# Schematic.net
KiCad netlist of a schematic drawn in Altium Designer
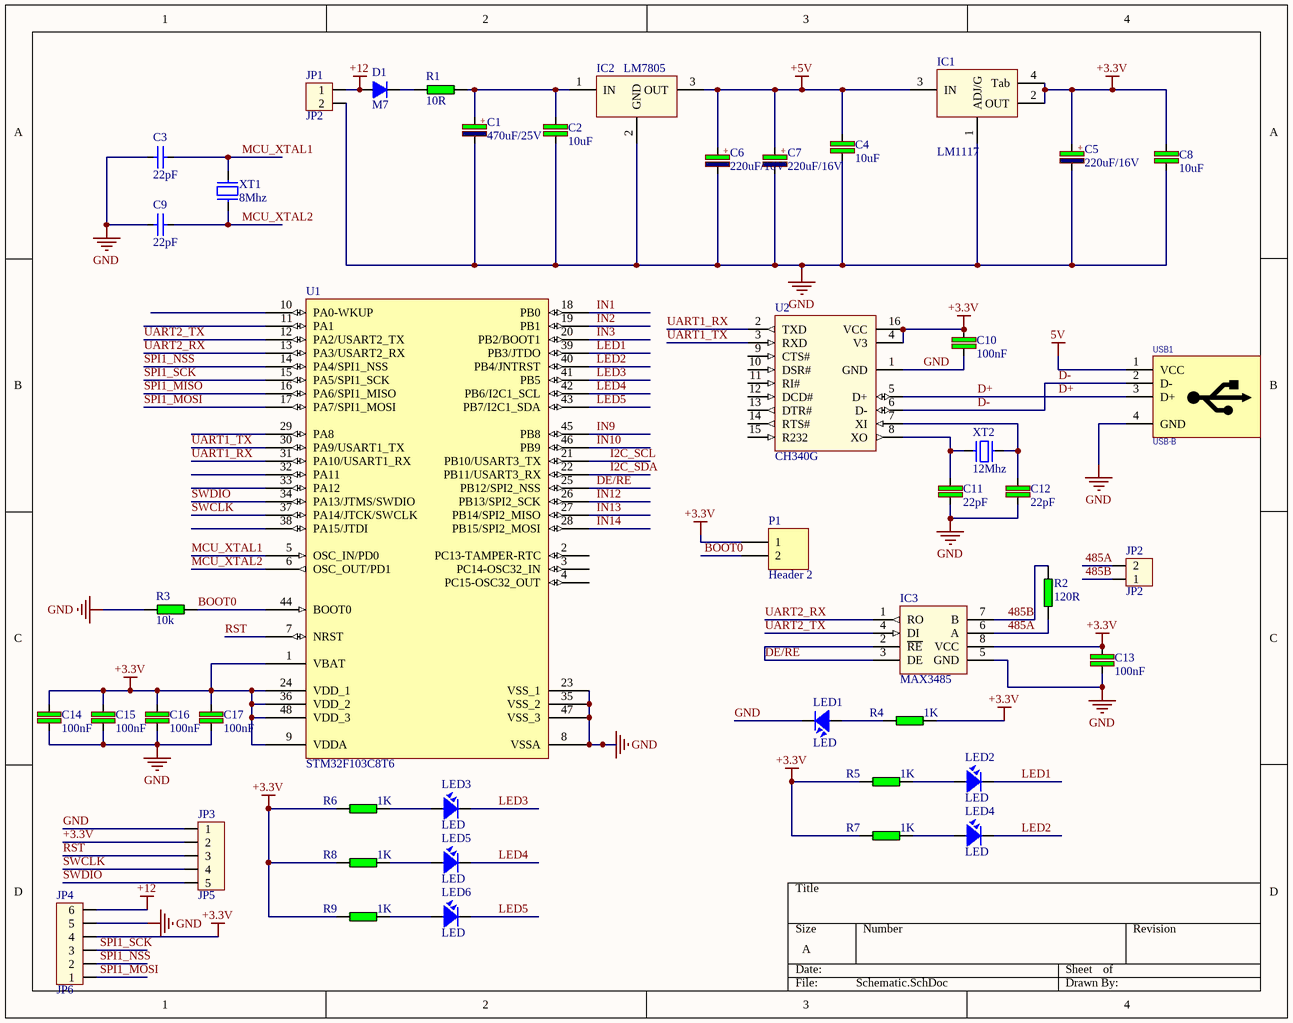
[diagram p0: Schematic.SchDoc]

(export (version "E")
  (design (tool "Eeschema 10.0.6"))
  (components
    (comp (ref "C1")
      (value "470uF/25V")
      (footprint "CP_1000UF/25V_NAM - cao")
      (description "470uF/35V")
      (fields (field (name "MANUFACTURER") "Würth Elektronik") (field (name "PART NUMBER") "860020575014"))
      (libsource (lib "Anh_Trung") (part "CP4"))
    )
    (comp (ref "C2")
      (value "10uF")
      (footprint "C-0805")
      (description "Cap SMD")
      (libsource (lib "") (part "C_1"))
    )
    (comp (ref "C3")
      (value "22pF")
      (footprint "CAP_0805")
      (description "Capacitor")
      (fields (field (name "PUBLISHER") "Altium Limited"))
      (libsource (lib "My Library") (part "CapSMD"))
    )
    (comp (ref "C4")
      (value "10uF")
      (footprint "C-0805")
      (description "Cap SMD")
      (libsource (lib "") (part "C_1"))
    )
    (comp (ref "C5")
      (value "220uF/16V")
      (footprint "CA-ALU-5L")
      (description "Cap 100uF/35V - 470uF/16V")
      (libsource (lib "Anh_Trung") (part "CP3"))
    )
    (comp (ref "C6")
      (value "220uF/16V")
      (footprint "CA-ALU-5L")
      (description "Cap 100uF/35V - 470uF/16V")
      (libsource (lib "Anh_Trung") (part "CP3"))
    )
    (comp (ref "C7")
      (value "220uF/16V")
      (footprint "CA-ALU-5L")
      (description "Cap 100uF/35V - 470uF/16V")
      (libsource (lib "Anh_Trung") (part "CP3"))
    )
    (comp (ref "C8")
      (value "10uF")
      (footprint "C-0805")
      (description "Cap SMD")
      (libsource (lib "") (part "C_1"))
    )
    (comp (ref "C9")
      (value "22pF")
      (footprint "CAP_0805")
      (description "Capacitor")
      (fields (field (name "PUBLISHER") "Altium Limited"))
      (libsource (lib "My Library") (part "CapSMD"))
    )
    (comp (ref "C10")
      (value "100nF")
      (footprint "C-0805")
      (description "Cap SMD")
      (fields
        (field (name "MANUFACTURER") "Samsung Electro-Mechanics")
        (field (name "PART NUMBER") "CL21B104KBCNNWC")
      )
      (libsource (lib "") (part "C_1"))
    )
    (comp (ref "C11")
      (value "22pF")
      (footprint "C-0805")
      (description "Cap SMD")
      (fields
        (field (name "MANUFACTURER") "Samsung Electro-Mechanics")
        (field (name "PART NUMBER") "CL21C220JBANFNC")
      )
      (libsource (lib "") (part "C_1"))
    )
    (comp (ref "C12")
      (value "22pF")
      (footprint "C-0805")
      (description "Cap SMD")
      (fields
        (field (name "MANUFACTURER") "Samsung Electro-Mechanics")
        (field (name "PART NUMBER") "CL21C220JBANFNC")
      )
      (libsource (lib "") (part "C_1"))
    )
    (comp (ref "C13")
      (value "100nF")
      (footprint "C-0805")
      (description "Cap SMD")
      (fields
        (field (name "MANUFACTURER") "Samsung Electro-Mechanics")
        (field (name "PART NUMBER") "CL21B104KBCNNWC")
      )
      (libsource (lib "Anh_Trung") (part "C"))
    )
    (comp (ref "C14")
      (value "100nF")
      (footprint "C-0805")
      (description "Cap SMD")
      (libsource (lib "heromap") (part "C"))
    )
    (comp (ref "C15")
      (value "100nF")
      (footprint "C-0805")
      (description "Cap SMD")
      (libsource (lib "heromap") (part "C"))
    )
    (comp (ref "C16")
      (value "100nF")
      (footprint "C-0805")
      (description "Cap SMD")
      (libsource (lib "heromap") (part "C"))
    )
    (comp (ref "C17")
      (value "100nF")
      (footprint "C-0805")
      (description "Cap SMD")
      (libsource (lib "heromap") (part "C"))
    )
    (comp (ref "D1")
      (value "M7")
      (footprint "SMA11")
      (description "Diode 1A")
      (libsource (lib "Anh_Trung") (part "D1A"))
    )
    (comp (ref "IC1")
      (value "LM1117")
      (footprint "SOT223-4N")
      (description "3v3")
      (libsource (lib "My Library") (part "LM1117"))
    )
    (comp (ref "IC2")
      (value "LM7805")
      (footprint "TO-252 7805")
      (description "On ap +, from + 5 to + 24VDC")
      (libsource (lib "Anh_Trung") (part "LM78xx"))
    )
    (comp (ref "IC3")
      (value "MAX3485")
      (footprint "SOIC-8")
      (description "IC TRANSCEIVER HALF 1/1 SOT23-8")
      (fields (field (name "MANUFACTURER") "Maxim Integrated") (field (name "PART NUMBER") "MAX3362EKA+T"))
      (libsource (lib "Anh_Trung") (part "MAX3362EKA+T"))
    )
    (comp (ref "JP1")
      (value "JP2")
      (footprint "KF2-5.08T")
      (description "Connector 2")
      (libsource (lib "") (part "Con2_1"))
    )
    (comp (ref "JP2")
      (value "JP2")
      (footprint "KF2-5.08T")
      (description "Connector 2")
      (libsource (lib "Anh_Trung") (part "Con2"))
    )
    (comp (ref "JP3")
      (value "JP5")
      (footprint "JP5-D1T")
      (description "Connector 5")
      (libsource (lib "Anh_Trung") (part "Con5"))
    )
    (comp (ref "JP4")
      (value "JP6")
      (footprint "CON6")
      (description "Connector 6")
      (libsource (lib "My Library") (part "Con6"))
    )
    (comp (ref "LED1")
      (value "LED")
      (footprint "LED-0805-Red")
      (description "LED Single colour Green and Red")
      (libsource (lib "My Library") (part "LED"))
    )
    (comp (ref "LED2")
      (value "LED")
      (footprint "LED-0805-Red")
      (description "LED Single colour Green and Red")
      (libsource (lib "My Library") (part "LED"))
    )
    (comp (ref "LED3")
      (value "LED")
      (footprint "LED-3")
      (description "LED Single colour Green and Red")
      (libsource (lib "VioletofSun") (part "LED"))
    )
    (comp (ref "LED4")
      (value "LED")
      (footprint "LED-0805-Red")
      (description "LED Single colour Green and Red")
      (libsource (lib "My Library") (part "LED"))
    )
    (comp (ref "LED5")
      (value "LED")
      (footprint "LED-3")
      (description "LED Single colour Green and Red")
      (libsource (lib "VioletofSun") (part "LED"))
    )
    (comp (ref "LED6")
      (value "LED")
      (footprint "LED-3")
      (description "LED Single colour Green and Red")
      (libsource (lib "VioletofSun") (part "LED"))
    )
    (comp (ref "P1")
      (value "Header 2")
      (footprint "HDR1X2")
      (description "Header, 2-Pin")
      (fields (field (name "PUBLISHER") "Altium Limited"))
      (libsource (lib "My Library") (part "Header 2"))
    )
    (comp (ref "R1")
      (value "10R")
      (footprint "R-1206")
      (description "Resistor 1/4W")
      (libsource (lib "") (part "RES_1"))
    )
    (comp (ref "R2")
      (value "120R")
      (footprint "R-0805")
      (description "Resistor 1/4W")
      (libsource (lib "heromap") (part "RES"))
    )
    (comp (ref "R3")
      (value "10k")
      (footprint "R-0805")
      (description "Resistor 1/4W")
      (libsource (lib "") (part "RES_3"))
    )
    (comp (ref "R4")
      (value "1K")
      (footprint "R-0805")
      (description "Resistor 1/4W")
      (libsource (lib "") (part "RES_2"))
    )
    (comp (ref "R5")
      (value "1K")
      (footprint "R-0805")
      (description "Resistor 1/4W")
      (libsource (lib "") (part "RES_2"))
    )
    (comp (ref "R6")
      (value "1K")
      (footprint "R-0805")
      (description "Resistor 1/4W")
      (libsource (lib "") (part "RES_2"))
    )
    (comp (ref "R7")
      (value "1K")
      (footprint "R-0805")
      (description "Resistor 1/4W")
      (libsource (lib "") (part "RES_2"))
    )
    (comp (ref "R8")
      (value "1K")
      (footprint "R-0805")
      (description "Resistor 1/4W")
      (libsource (lib "") (part "RES_2"))
    )
    (comp (ref "R9")
      (value "1K")
      (footprint "R-0805")
      (description "Resistor 1/4W")
      (libsource (lib "") (part "RES_2"))
    )
    (comp (ref "U1")
      (value "STM32F103C8T6")
      (footprint "LQFP48_L")
      (libsource (lib "heromap") (part "STM32F103C8T6"))
    )
    (comp (ref "U2")
      (value "CH340G")
      (footprint "SOIC-16")
      (description "USB to UART Interface")
      (fields (field (name "MANUFACTURER") "WCH"))
      (libsource (lib "Anh_Trung") (part "CH340G"))
    )
    (comp (ref "USB1")
      (value "USB-B")
      (footprint "USB-B")
      (description "CONN USB 2.0 RT ANGLE TYPE B")
      (fields (field (name "MANUFACTURER") "Stewart Connector") (field (name "PART NUMBER") "SS-52300-001"))
      (libsource (lib "Anh_Trung") (part "USB-B"))
    )
    (comp (ref "XT1")
      (value "8Mhz")
      (footprint "XTAL-RU49/4")
      (description "CRYSTAL 12.0000MHZ 18PF SMD")
      (fields
        (field (name "MANUFACTURER") "IQD Frequency Products")
        (field (name "PART NUMBER") "LFXTAL036356REEL")
      )
      (libsource (lib "Anh_Trung") (part "XT2"))
    )
    (comp (ref "XT2")
      (value "12Mhz")
      (footprint "XTAL-RU49/4")
      (description "CRYSTAL 12.0000MHZ 18PF SMD")
      (fields
        (field (name "MANUFACTURER") "IQD Frequency Products")
        (field (name "PART NUMBER") "LFXTAL036356REEL")
      )
      (libsource (lib "Anh_Trung") (part "XT2"))
    )
  )
  (nets
    (net (code "1") (name "+3.3V") (class "Default")
      (node (ref "C10") (pin "2") (pinfunction "2_2") (pintype "passive"))
      (node (ref "C13") (pin "1") (pinfunction "1_1") (pintype "passive"))
      (node (ref "C14") (pin "1") (pinfunction "1_1") (pintype "passive"))
      (node (ref "C15") (pin "1") (pinfunction "1_1") (pintype "passive"))
      (node (ref "C16") (pin "1") (pinfunction "1_1") (pintype "passive"))
      (node (ref "C17") (pin "1") (pinfunction "1_1") (pintype "passive"))
      (node (ref "C5") (pin "1") (pinfunction "1_1") (pintype "passive"))
      (node (ref "C8") (pin "2") (pinfunction "2_2") (pintype "passive"))
      (node (ref "IC1") (pin "2") (pinfunction "OUT_2") (pintype "passive"))
      (node (ref "IC1") (pin "4") (pinfunction "Tab_4") (pintype "passive"))
      (node (ref "IC3") (pin "8") (pinfunction "VCC_8") (pintype "passive"))
      (node (ref "JP3") (pin "2") (pinfunction "2_2") (pintype "passive"))
      (node (ref "JP4") (pin "4") (pinfunction "4_4") (pintype "passive"))
      (node (ref "P1") (pin "1") (pinfunction "1_1") (pintype "passive"))
      (node (ref "R4") (pin "1") (pinfunction "1_1") (pintype "passive"))
      (node (ref "R5") (pin "2") (pinfunction "2_2") (pintype "passive"))
      (node (ref "R6") (pin "2") (pinfunction "2_2") (pintype "passive"))
      (node (ref "R7") (pin "2") (pinfunction "2_2") (pintype "passive"))
      (node (ref "R8") (pin "2") (pinfunction "2_2") (pintype "passive"))
      (node (ref "R9") (pin "2") (pinfunction "2_2") (pintype "passive"))
      (node (ref "U1") (pin "1") (pinfunction "VBAT_1") (pintype "power_in"))
      (node (ref "U1") (pin "24") (pinfunction "VDD_1_24") (pintype "power_in"))
      (node (ref "U1") (pin "36") (pinfunction "VDD_2_36") (pintype "power_in"))
      (node (ref "U1") (pin "48") (pinfunction "VDD_3_48") (pintype "power_in"))
      (node (ref "U1") (pin "9") (pinfunction "VDDA_9") (pintype "power_in"))
      (node (ref "U2") (pin "16") (pinfunction "VCC_16") (pintype "power_in"))
      (node (ref "U2") (pin "4") (pinfunction "V3_4") (pintype "passive"))
    )
    (net (code "2") (name "+5V") (class "Default")
      (node (ref "C4") (pin "2") (pinfunction "2_2") (pintype "passive"))
      (node (ref "C6") (pin "1") (pinfunction "1_1") (pintype "passive"))
      (node (ref "C7") (pin "1") (pinfunction "1_1") (pintype "passive"))
      (node (ref "IC1") (pin "3") (pinfunction "IN_3") (pintype "passive"))
      (node (ref "IC2") (pin "3") (pinfunction "OUT_3") (pintype "passive"))
    )
    (net (code "3") (name "+12") (class "Default")
      (node (ref "D1") (pin "1") (pinfunction "A_1") (pintype "passive"))
      (node (ref "JP1") (pin "1") (pinfunction "1_1") (pintype "passive"))
      (node (ref "JP4") (pin "6") (pinfunction "6_6") (pintype "passive"))
    )
    (net (code "4") (name "/485A") (class "Default")
      (node (ref "IC3") (pin "6") (pinfunction "A_6") (pintype "passive"))
      (node (ref "JP2") (pin "2") (pinfunction "2_2") (pintype "passive"))
      (node (ref "R2") (pin "2") (pinfunction "2_2") (pintype "passive"))
    )
    (net (code "5") (name "/485B") (class "Default")
      (node (ref "IC3") (pin "7") (pinfunction "B_7") (pintype "passive"))
      (node (ref "JP2") (pin "1") (pinfunction "1_1") (pintype "passive"))
      (node (ref "R2") (pin "1") (pinfunction "1_1") (pintype "passive"))
    )
    (net (code "6") (name "/BOOT0") (class "Default")
      (node (ref "P1") (pin "2") (pinfunction "2_2") (pintype "passive"))
      (node (ref "R3") (pin "2") (pinfunction "2_2") (pintype "passive"))
      (node (ref "U1") (pin "44") (pinfunction "BOOT0_44") (pintype "input"))
    )
    (net (code "7") (name "/D+") (class "Default")
      (node (ref "U2") (pin "5") (pinfunction "D+_5") (pintype "bidirectional"))
      (node (ref "USB1") (pin "3") (pinfunction "D+_3") (pintype "passive"))
    )
    (net (code "8") (name "/D-") (class "Default")
      (node (ref "U2") (pin "6") (pinfunction "D-_6") (pintype "bidirectional"))
      (node (ref "USB1") (pin "2") (pinfunction "D-_2") (pintype "passive"))
    )
    (net (code "9") (name "/DE{slash}RE") (class "Default")
      (node (ref "IC3") (pin "2") (pinfunction "~{RE}_2") (pintype "passive"))
      (node (ref "IC3") (pin "3") (pinfunction "DE_3") (pintype "passive"))
      (node (ref "U1") (pin "25") (pinfunction "PB12/SPI2_NSS_25") (pintype "bidirectional"))
    )
    (net (code "10") (name "/I2C_SCL") (class "Default")
      (node (ref "U1") (pin "21") (pinfunction "PB10/USART3_TX_21") (pintype "bidirectional"))
    )
    (net (code "11") (name "/I2C_SDA") (class "Default")
      (node (ref "U1") (pin "22") (pinfunction "PB11/USART3_RX_22") (pintype "bidirectional"))
    )
    (net (code "12") (name "/IN1") (class "Default")
      (node (ref "U1") (pin "18") (pinfunction "PB0_18") (pintype "bidirectional"))
    )
    (net (code "13") (name "/IN2") (class "Default")
      (node (ref "U1") (pin "19") (pinfunction "PB1_19") (pintype "bidirectional"))
    )
    (net (code "14") (name "/IN3") (class "Default")
      (node (ref "U1") (pin "20") (pinfunction "PB2/BOOT1_20") (pintype "bidirectional"))
    )
    (net (code "15") (name "/IN9") (class "Default")
      (node (ref "U1") (pin "45") (pinfunction "PB8_45") (pintype "bidirectional"))
    )
    (net (code "16") (name "/IN10") (class "Default")
      (node (ref "U1") (pin "46") (pinfunction "PB9_46") (pintype "bidirectional"))
    )
    (net (code "17") (name "/IN12") (class "Default")
      (node (ref "U1") (pin "26") (pinfunction "PB13/SPI2_SCK_26") (pintype "bidirectional"))
    )
    (net (code "18") (name "/IN13") (class "Default")
      (node (ref "U1") (pin "27") (pinfunction "PB14/SPI2_MISO_27") (pintype "bidirectional"))
    )
    (net (code "19") (name "/IN14") (class "Default")
      (node (ref "U1") (pin "28") (pinfunction "PB15/SPI2_MOSI_28") (pintype "bidirectional"))
    )
    (net (code "20") (name "/LED1") (class "Default")
      (node (ref "LED2") (pin "2") (pinfunction "2_2") (pintype "passive"))
      (node (ref "U1") (pin "39") (pinfunction "PB3/JTDO_39") (pintype "bidirectional"))
    )
    (net (code "21") (name "/LED2") (class "Default")
      (node (ref "LED4") (pin "2") (pinfunction "2_2") (pintype "passive"))
      (node (ref "U1") (pin "40") (pinfunction "PB4/JNTRST_40") (pintype "bidirectional"))
    )
    (net (code "22") (name "/LED3") (class "Default")
      (node (ref "LED3") (pin "2") (pinfunction "2_2") (pintype "passive"))
      (node (ref "U1") (pin "41") (pinfunction "PB5_41") (pintype "bidirectional"))
    )
    (net (code "23") (name "/LED4") (class "Default")
      (node (ref "LED5") (pin "2") (pinfunction "2_2") (pintype "passive"))
      (node (ref "U1") (pin "42") (pinfunction "PB6/I2C1_SCL_42") (pintype "bidirectional"))
    )
    (net (code "24") (name "/LED5") (class "Default")
      (node (ref "LED6") (pin "2") (pinfunction "2_2") (pintype "passive"))
      (node (ref "U1") (pin "43") (pinfunction "PB7/I2C1_SDA_43") (pintype "bidirectional"))
    )
    (net (code "25") (name "/MCU_XTAL1") (class "Default")
      (node (ref "C3") (pin "1") (pinfunction "1_1") (pintype "passive"))
      (node (ref "U1") (pin "5") (pinfunction "OSC_IN/PD0_5") (pintype "input"))
      (node (ref "XT1") (pin "1") (pinfunction "1_1") (pintype "passive"))
    )
    (net (code "26") (name "/MCU_XTAL2") (class "Default")
      (node (ref "C9") (pin "1") (pinfunction "1_1") (pintype "passive"))
      (node (ref "U1") (pin "6") (pinfunction "OSC_OUT/PD1_6") (pintype "output"))
      (node (ref "XT1") (pin "2") (pinfunction "2_2") (pintype "passive"))
    )
    (net (code "27") (name "/RST") (class "Default")
      (node (ref "JP3") (pin "3") (pinfunction "3_3") (pintype "passive"))
      (node (ref "U1") (pin "7") (pinfunction "NRST_7") (pintype "bidirectional"))
    )
    (net (code "28") (name "/SPI1_MISO") (class "Default")
      (node (ref "U1") (pin "16") (pinfunction "PA6/SPI1_MISO_16") (pintype "bidirectional"))
    )
    (net (code "29") (name "/SPI1_MOSI") (class "Default")
      (node (ref "JP4") (pin "1") (pinfunction "1_1") (pintype "passive"))
      (node (ref "U1") (pin "17") (pinfunction "PA7/SPI1_MOSI_17") (pintype "bidirectional"))
    )
    (net (code "30") (name "/SPI1_NSS") (class "Default")
      (node (ref "JP4") (pin "2") (pinfunction "2_2") (pintype "passive"))
      (node (ref "U1") (pin "14") (pinfunction "PA4/SPI1_NSS_14") (pintype "bidirectional"))
    )
    (net (code "31") (name "/SPI1_SCK") (class "Default")
      (node (ref "JP4") (pin "3") (pinfunction "3_3") (pintype "passive"))
      (node (ref "U1") (pin "15") (pinfunction "PA5/SPI1_SCK_15") (pintype "bidirectional"))
    )
    (net (code "32") (name "/SWCLK") (class "Default")
      (node (ref "JP3") (pin "4") (pinfunction "4_4") (pintype "passive"))
      (node (ref "U1") (pin "37") (pinfunction "PA14/JTCK/SWCLK_37") (pintype "bidirectional"))
    )
    (net (code "33") (name "/SWDIO") (class "Default")
      (node (ref "JP3") (pin "5") (pinfunction "5_5") (pintype "passive"))
      (node (ref "U1") (pin "34") (pinfunction "PA13/JTMS/SWDIO_34") (pintype "bidirectional"))
    )
    (net (code "34") (name "/UART1_RX") (class "Default")
      (node (ref "U1") (pin "31") (pinfunction "PA10/USART1_RX_31") (pintype "bidirectional"))
      (node (ref "U2") (pin "2") (pinfunction "TXD_2") (pintype "output"))
    )
    (net (code "35") (name "/UART1_TX") (class "Default")
      (node (ref "U1") (pin "30") (pinfunction "PA9/USART1_TX_30") (pintype "bidirectional"))
      (node (ref "U2") (pin "3") (pinfunction "RXD_3") (pintype "input"))
    )
    (net (code "36") (name "/UART2_RX") (class "Default")
      (node (ref "IC3") (pin "1") (pinfunction "RO_1") (pintype "output"))
      (node (ref "U1") (pin "13") (pinfunction "PA3/USART2_RX_13") (pintype "bidirectional"))
    )
    (net (code "37") (name "/UART2_TX") (class "Default")
      (node (ref "IC3") (pin "4") (pinfunction "DI_4") (pintype "input"))
      (node (ref "U1") (pin "12") (pinfunction "PA2/USART2_TX_12") (pintype "bidirectional"))
    )
    (net (code "38") (name "5V") (class "Default")
      (node (ref "USB1") (pin "1") (pinfunction "VCC_1") (pintype "passive"))
    )
    (net (code "39") (name "GND") (class "Default")
      (node (ref "C1") (pin "2") (pinfunction "2_2") (pintype "passive"))
      (node (ref "C10") (pin "1") (pinfunction "1_1") (pintype "passive"))
      (node (ref "C11") (pin "1") (pinfunction "1_1") (pintype "passive"))
      (node (ref "C12") (pin "1") (pinfunction "1_1") (pintype "passive"))
      (node (ref "C13") (pin "2") (pinfunction "2_2") (pintype "passive"))
      (node (ref "C14") (pin "2") (pinfunction "2_2") (pintype "passive"))
      (node (ref "C15") (pin "2") (pinfunction "2_2") (pintype "passive"))
      (node (ref "C16") (pin "2") (pinfunction "2_2") (pintype "passive"))
      (node (ref "C17") (pin "2") (pinfunction "2_2") (pintype "passive"))
      (node (ref "C2") (pin "1") (pinfunction "1_1") (pintype "passive"))
      (node (ref "C3") (pin "2") (pinfunction "2_2") (pintype "passive"))
      (node (ref "C4") (pin "1") (pinfunction "1_1") (pintype "passive"))
      (node (ref "C5") (pin "2") (pinfunction "2_2") (pintype "passive"))
      (node (ref "C6") (pin "2") (pinfunction "2_2") (pintype "passive"))
      (node (ref "C7") (pin "2") (pinfunction "2_2") (pintype "passive"))
      (node (ref "C8") (pin "1") (pinfunction "1_1") (pintype "passive"))
      (node (ref "C9") (pin "2") (pinfunction "2_2") (pintype "passive"))
      (node (ref "IC1") (pin "1") (pinfunction "ADJ/G_1") (pintype "passive"))
      (node (ref "IC2") (pin "2") (pinfunction "GND_2") (pintype "passive"))
      (node (ref "IC3") (pin "5") (pinfunction "GND_5") (pintype "passive"))
      (node (ref "JP1") (pin "2") (pinfunction "2_2") (pintype "passive"))
      (node (ref "JP3") (pin "1") (pinfunction "1_1") (pintype "passive"))
      (node (ref "JP4") (pin "5") (pinfunction "5_5") (pintype "passive"))
      (node (ref "LED1") (pin "2") (pinfunction "2_2") (pintype "passive"))
      (node (ref "R3") (pin "1") (pinfunction "1_1") (pintype "passive"))
      (node (ref "U1") (pin "23") (pinfunction "VSS_1_23") (pintype "power_in"))
      (node (ref "U1") (pin "35") (pinfunction "VSS_2_35") (pintype "power_in"))
      (node (ref "U1") (pin "47") (pinfunction "VSS_3_47") (pintype "power_in"))
      (node (ref "U1") (pin "8") (pinfunction "VSSA_8") (pintype "power_in"))
      (node (ref "U2") (pin "1") (pinfunction "GND_1") (pintype "passive"))
      (node (ref "USB1") (pin "4") (pinfunction "GND_4") (pintype "passive"))
    )
    (net (code "40") (name "Net-(D1-K)") (class "Default")
      (node (ref "D1") (pin "2") (pinfunction "K_2") (pintype "passive"))
      (node (ref "R1") (pin "1") (pinfunction "1_1") (pintype "passive"))
    )
    (net (code "41") (name "Net-(IC2-IN)") (class "Default")
      (node (ref "C1") (pin "1") (pinfunction "1_1") (pintype "passive"))
      (node (ref "C2") (pin "2") (pinfunction "2_2") (pintype "passive"))
      (node (ref "IC2") (pin "1") (pinfunction "IN_1") (pintype "passive"))
      (node (ref "R1") (pin "2") (pinfunction "2_2") (pintype "passive"))
    )
    (net (code "42") (name "Net-(LED1-Pad1)") (class "Default")
      (node (ref "LED1") (pin "1") (pinfunction "1_1") (pintype "passive"))
      (node (ref "R4") (pin "2") (pinfunction "2_2") (pintype "passive"))
    )
    (net (code "43") (name "Net-(LED2-Pad1)") (class "Default")
      (node (ref "LED2") (pin "1") (pinfunction "1_1") (pintype "passive"))
      (node (ref "R5") (pin "1") (pinfunction "1_1") (pintype "passive"))
    )
    (net (code "44") (name "Net-(LED3-Pad1)") (class "Default")
      (node (ref "LED3") (pin "1") (pinfunction "1_1") (pintype "passive"))
      (node (ref "R6") (pin "1") (pinfunction "1_1") (pintype "passive"))
    )
    (net (code "45") (name "Net-(LED4-Pad1)") (class "Default")
      (node (ref "LED4") (pin "1") (pinfunction "1_1") (pintype "passive"))
      (node (ref "R7") (pin "1") (pinfunction "1_1") (pintype "passive"))
    )
    (net (code "46") (name "Net-(LED5-Pad1)") (class "Default")
      (node (ref "LED5") (pin "1") (pinfunction "1_1") (pintype "passive"))
      (node (ref "R8") (pin "1") (pinfunction "1_1") (pintype "passive"))
    )
    (net (code "47") (name "Net-(LED6-Pad1)") (class "Default")
      (node (ref "LED6") (pin "1") (pinfunction "1_1") (pintype "passive"))
      (node (ref "R9") (pin "1") (pinfunction "1_1") (pintype "passive"))
    )
    (net (code "48") (name "Net-(U2-XI)") (class "Default")
      (node (ref "C12") (pin "2") (pinfunction "2_2") (pintype "passive"))
      (node (ref "U2") (pin "7") (pinfunction "XI_7") (pintype "input"))
      (node (ref "XT2") (pin "2") (pinfunction "2_2") (pintype "passive"))
    )
    (net (code "49") (name "Net-(U2-XO)") (class "Default")
      (node (ref "C11") (pin "2") (pinfunction "2_2") (pintype "passive"))
      (node (ref "U2") (pin "8") (pinfunction "XO_8") (pintype "output"))
      (node (ref "XT2") (pin "1") (pinfunction "1_1") (pintype "passive"))
    )
    (net (code "50") (name "unconnected-(U1-PA0-WKUP-Pad10)") (class "Default")
      (node (ref "U1") (pin "10") (pinfunction "PA0-WKUP_10") (pintype "bidirectional"))
    )
    (net (code "51") (name "unconnected-(U1-PA1-Pad11)") (class "Default")
      (node (ref "U1") (pin "11") (pinfunction "PA1_11") (pintype "bidirectional"))
    )
    (net (code "52") (name "unconnected-(U1-PA8-Pad29)") (class "Default")
      (node (ref "U1") (pin "29") (pinfunction "PA8_29") (pintype "bidirectional"))
    )
    (net (code "53") (name "unconnected-(U1-PA11-Pad32)") (class "Default")
      (node (ref "U1") (pin "32") (pinfunction "PA11_32") (pintype "bidirectional"))
    )
    (net (code "54") (name "unconnected-(U1-PA12-Pad33)") (class "Default")
      (node (ref "U1") (pin "33") (pinfunction "PA12_33") (pintype "bidirectional"))
    )
    (net (code "55") (name "unconnected-(U1-PA15{slash}JTDI-Pad38)") (class "Default")
      (node (ref "U1") (pin "38") (pinfunction "PA15/JTDI_38") (pintype "bidirectional"))
    )
    (net (code "56") (name "unconnected-(U1-PC13-TAMPER-RTC-Pad2)") (class "Default")
      (node (ref "U1") (pin "2") (pinfunction "PC13-TAMPER-RTC_2") (pintype "bidirectional"))
    )
    (net (code "57") (name "unconnected-(U1-PC14-OSC32_IN-Pad3)") (class "Default")
      (node (ref "U1") (pin "3") (pinfunction "PC14-OSC32_IN_3") (pintype "bidirectional"))
    )
    (net (code "58") (name "unconnected-(U1-PC15-OSC32_OUT-Pad4)") (class "Default")
      (node (ref "U1") (pin "4") (pinfunction "PC15-OSC32_OUT_4") (pintype "bidirectional"))
    )
    (net (code "59") (name "unconnected-(U2-CTS#-Pad9)") (class "Default")
      (node (ref "U2") (pin "9") (pinfunction "CTS#_9") (pintype "input"))
    )
    (net (code "60") (name "unconnected-(U2-DCD#-Pad12)") (class "Default")
      (node (ref "U2") (pin "12") (pinfunction "DCD#_12") (pintype "input"))
    )
    (net (code "61") (name "unconnected-(U2-DSR#-Pad10)") (class "Default")
      (node (ref "U2") (pin "10") (pinfunction "DSR#_10") (pintype "input"))
    )
    (net (code "62") (name "unconnected-(U2-DTR#-Pad13)") (class "Default")
      (node (ref "U2") (pin "13") (pinfunction "DTR#_13") (pintype "output"))
    )
    (net (code "63") (name "unconnected-(U2-R232-Pad15)") (class "Default")
      (node (ref "U2") (pin "15") (pinfunction "R232_15") (pintype "input"))
    )
    (net (code "64") (name "unconnected-(U2-RI#-Pad11)") (class "Default")
      (node (ref "U2") (pin "11") (pinfunction "RI#_11") (pintype "input"))
    )
    (net (code "65") (name "unconnected-(U2-RTS#-Pad14)") (class "Default")
      (node (ref "U2") (pin "14") (pinfunction "RTS#_14") (pintype "output"))
    )
  )
)
